# EnsembleEight.net
KiCad netlist of a schematic drawn in EAGLE
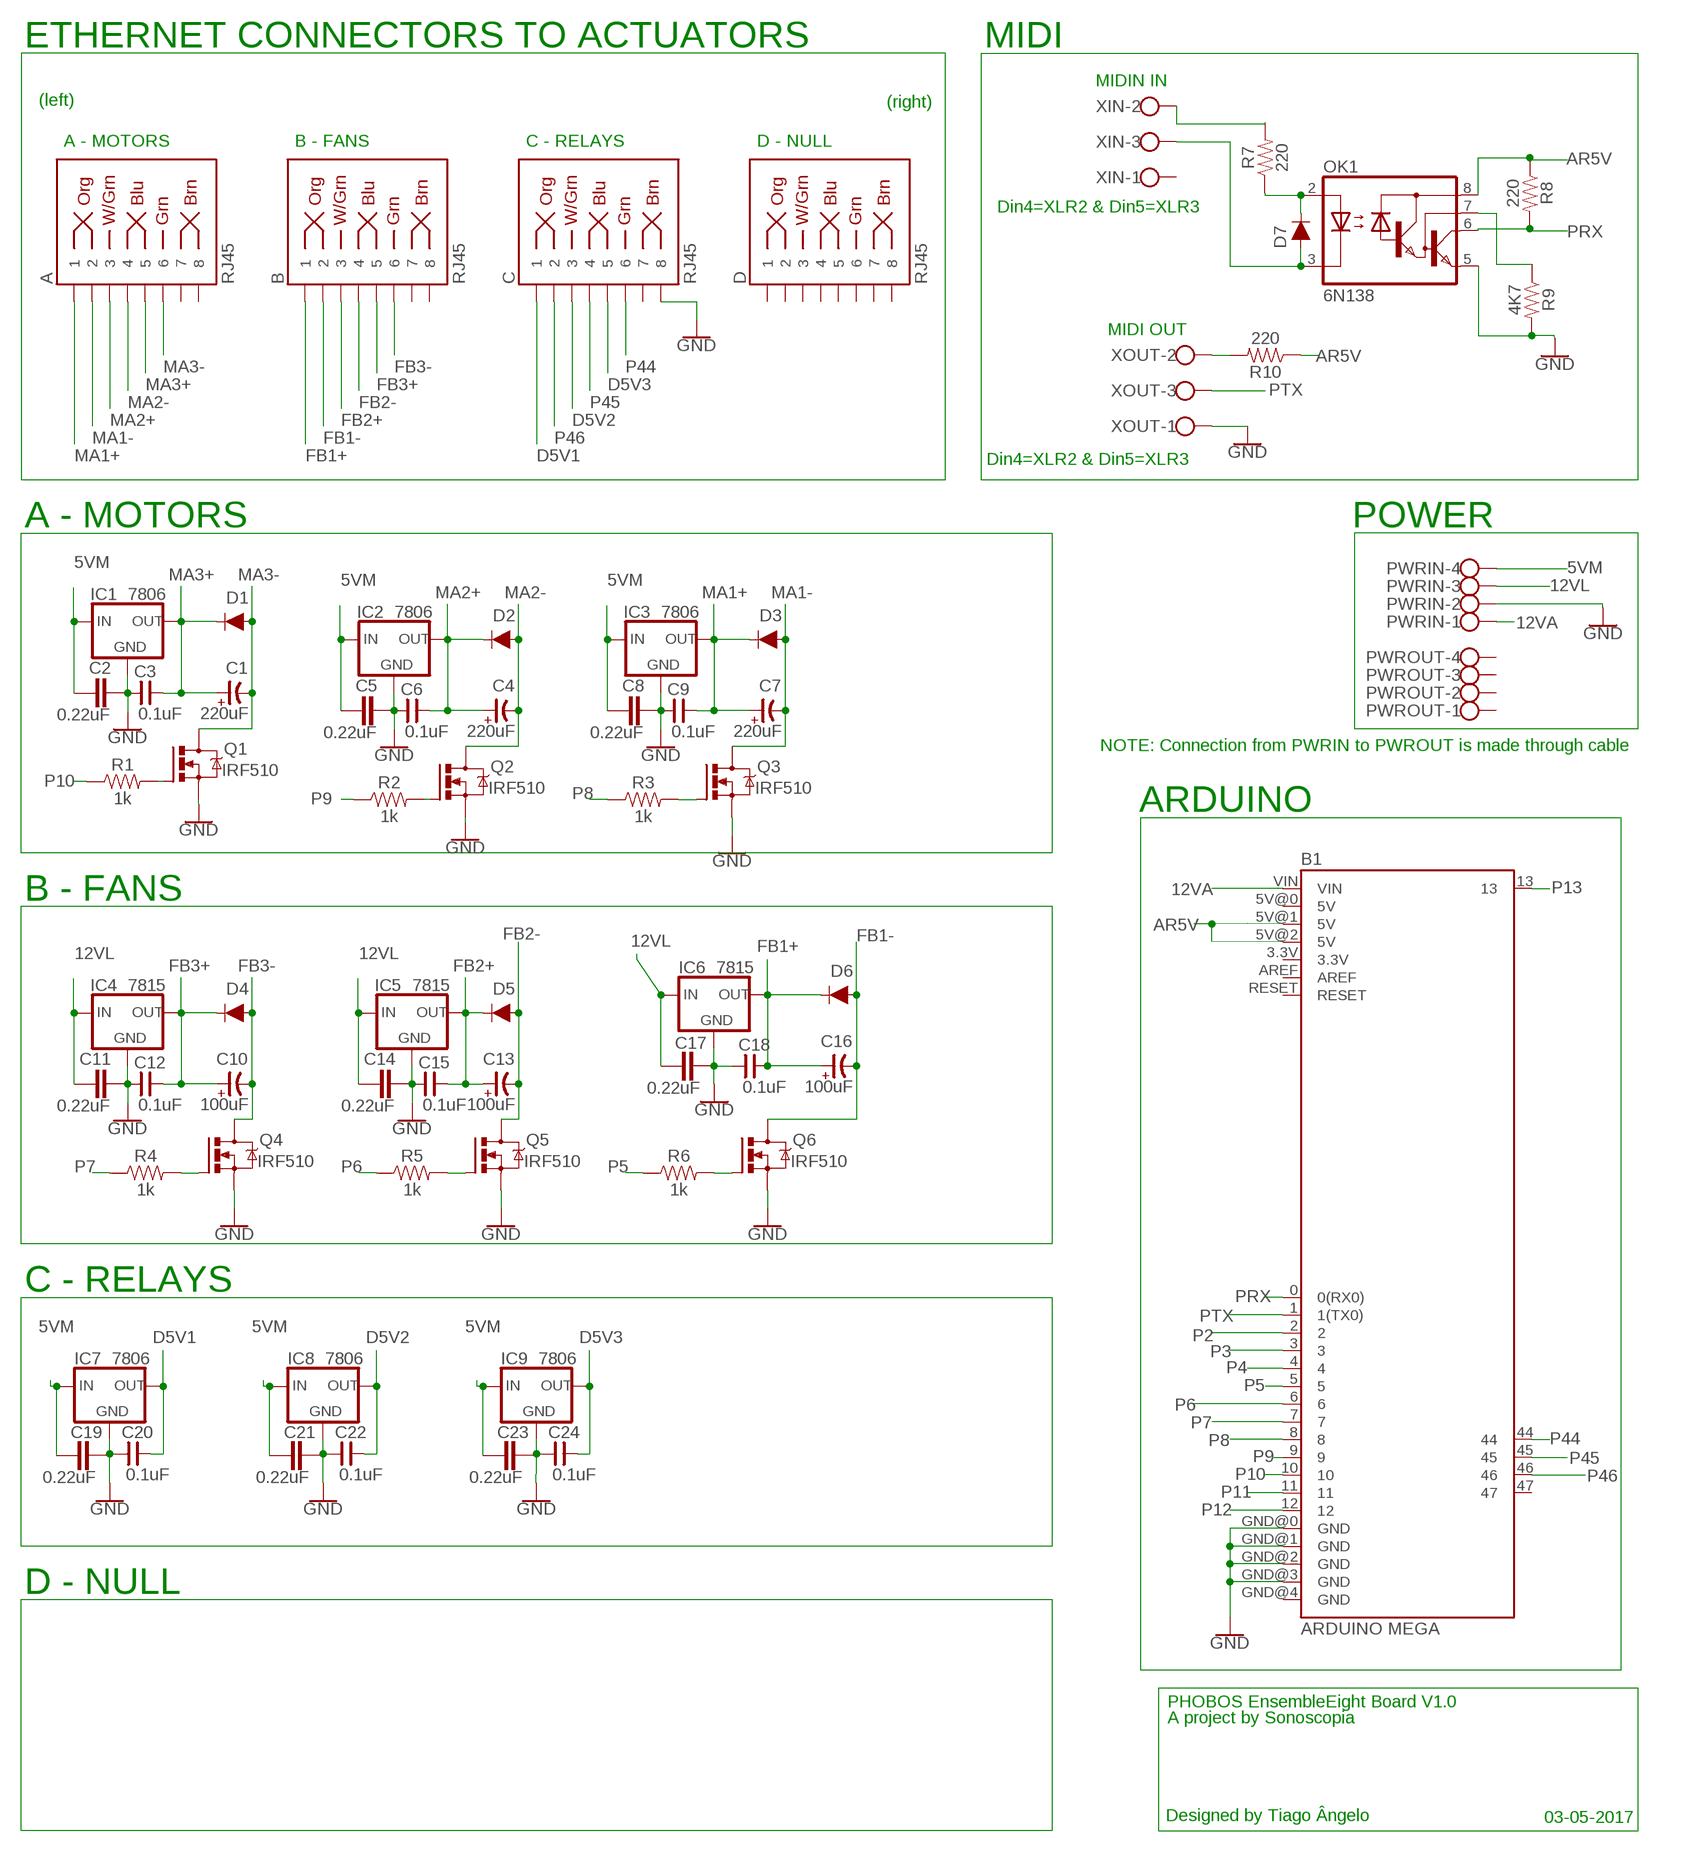
[diagram p0: schematic, sheet 1]

(export (version "E")
  (design (tool "Eeschema 10.0.6"))
  (components
    (comp (ref "A")
      (value "RJ45")
      (footprint "eagle-import:RJ45-8")
      (libsource (lib "eagle-import") (part "RJ45-8"))
    )
    (comp (ref "B")
      (value "RJ45")
      (footprint "eagle-import:RJ45-8")
      (libsource (lib "eagle-import") (part "RJ45-8"))
    )
    (comp (ref "B1")
      (value "ARDUINO MEGA")
      (footprint "eagle-import:ARDUINO_MEGA")
      (libsource (lib "eagle-import") (part "ARDUINO_MEGA_R3FULL"))
    )
    (comp (ref "C")
      (value "RJ45")
      (footprint "eagle-import:RJ45-8")
      (libsource (lib "eagle-import") (part "RJ45-8"))
    )
    (comp (ref "C1")
      (value "220uF")
      (footprint "eagle-import:E-035X080")
      (libsource (lib "eagle-import") (part "CP-E-035X080"))
    )
    (comp (ref "C2")
      (value "0.22uF")
      (footprint "eagle-import:C5B3")
      (libsource (lib "eagle-import") (part "C5/3"))
    )
    (comp (ref "C3")
      (value "0.1uF")
      (footprint "eagle-import:C025-050X025")
      (libsource (lib "eagle-import") (part "CNP-C025-050X025"))
    )
    (comp (ref "C4")
      (value "220uF")
      (footprint "eagle-import:E-035X080")
      (libsource (lib "eagle-import") (part "CP-E-035X080"))
    )
    (comp (ref "C5")
      (value "0.22uF")
      (footprint "eagle-import:C5B3")
      (libsource (lib "eagle-import") (part "C5/3"))
    )
    (comp (ref "C6")
      (value "0.1uF")
      (footprint "eagle-import:C025-050X025")
      (libsource (lib "eagle-import") (part "CNP-C025-050X025"))
    )
    (comp (ref "C7")
      (value "220uF")
      (footprint "eagle-import:E-035X080")
      (libsource (lib "eagle-import") (part "CP-E-035X080"))
    )
    (comp (ref "C8")
      (value "0.22uF")
      (footprint "eagle-import:C5B3")
      (libsource (lib "eagle-import") (part "C5/3"))
    )
    (comp (ref "C9")
      (value "0.1uF")
      (footprint "eagle-import:C025-050X025")
      (libsource (lib "eagle-import") (part "CNP-C025-050X025"))
    )
    (comp (ref "C10")
      (value "100uF")
      (footprint "eagle-import:CAP-MASTER_E-020X050")
      (libsource (lib "eagle-import") (part "CAP-MASTER_CP-E-020X050"))
    )
    (comp (ref "C11")
      (value "0.22uF")
      (footprint "eagle-import:C5B3")
      (libsource (lib "eagle-import") (part "C5/3"))
    )
    (comp (ref "C12")
      (value "0.1uF")
      (footprint "eagle-import:C025-050X025")
      (libsource (lib "eagle-import") (part "CNP-C025-050X025"))
    )
    (comp (ref "C13")
      (value "100uF")
      (footprint "eagle-import:CAP-MASTER_E-020X050")
      (libsource (lib "eagle-import") (part "CAP-MASTER_CP-E-020X050"))
    )
    (comp (ref "C14")
      (value "0.22uF")
      (footprint "eagle-import:C5B3")
      (libsource (lib "eagle-import") (part "C5/3"))
    )
    (comp (ref "C15")
      (value "0.1uF")
      (footprint "eagle-import:C025-050X025")
      (libsource (lib "eagle-import") (part "CNP-C025-050X025"))
    )
    (comp (ref "C16")
      (value "100uF")
      (footprint "eagle-import:CAP-MASTER_E-020X050")
      (libsource (lib "eagle-import") (part "CAP-MASTER_CP-E-020X050"))
    )
    (comp (ref "C17")
      (value "0.22uF")
      (footprint "eagle-import:C5B3")
      (libsource (lib "eagle-import") (part "C5/3"))
    )
    (comp (ref "C18")
      (value "0.1uF")
      (footprint "eagle-import:C025-050X025")
      (libsource (lib "eagle-import") (part "CNP-C025-050X025"))
    )
    (comp (ref "C19")
      (value "0.22uF")
      (footprint "eagle-import:C5B3")
      (libsource (lib "eagle-import") (part "C5/3"))
    )
    (comp (ref "C20")
      (value "0.1uF")
      (footprint "eagle-import:C025-050X025")
      (libsource (lib "eagle-import") (part "CNP-C025-050X025"))
    )
    (comp (ref "C21")
      (value "0.22uF")
      (footprint "eagle-import:C5B3")
      (libsource (lib "eagle-import") (part "C5/3"))
    )
    (comp (ref "C22")
      (value "0.1uF")
      (footprint "eagle-import:C025-050X025")
      (libsource (lib "eagle-import") (part "CNP-C025-050X025"))
    )
    (comp (ref "C23")
      (value "0.22uF")
      (footprint "eagle-import:C5B3")
      (libsource (lib "eagle-import") (part "C5/3"))
    )
    (comp (ref "C24")
      (value "0.1uF")
      (footprint "eagle-import:C025-050X025")
      (libsource (lib "eagle-import") (part "CNP-C025-050X025"))
    )
    (comp (ref "D")
      (value "RJ45")
      (footprint "eagle-import:RJ45-8")
      (libsource (lib "eagle-import") (part "RJ45-8"))
    )
    (comp (ref "D1")
      (value "1A/50V/1.1V")
      (footprint "eagle-import:DIODE-1N4001-KIT")
      (libsource (lib "eagle-import") (part "DIODE-KIT2"))
    )
    (comp (ref "D2")
      (value "1A/50V/1.1V")
      (footprint "eagle-import:DIODE-1N4001-KIT")
      (libsource (lib "eagle-import") (part "DIODE-KIT2"))
    )
    (comp (ref "D3")
      (value "1A/50V/1.1V")
      (footprint "eagle-import:DIODE-1N4001-KIT")
      (libsource (lib "eagle-import") (part "DIODE-KIT2"))
    )
    (comp (ref "D4")
      (value "1A/50V/1.1V")
      (footprint "eagle-import:DIODE-1N4001-KIT")
      (libsource (lib "eagle-import") (part "DIODE-KIT2"))
    )
    (comp (ref "D5")
      (value "1A/50V/1.1V")
      (footprint "eagle-import:DIODE-1N4001-KIT")
      (libsource (lib "eagle-import") (part "DIODE-KIT2"))
    )
    (comp (ref "D6")
      (value "1A/50V/1.1V")
      (footprint "eagle-import:DIODE-1N4001-KIT")
      (libsource (lib "eagle-import") (part "DIODE-KIT2"))
    )
    (comp (ref "D7")
      (value "200mA/100V/1V")
      (footprint "eagle-import:DIODE-1N4148")
      (libsource (lib "eagle-import") (part "DIODE-1N4148"))
    )
    (comp (ref "IC1")
      (value "7806")
      (footprint "eagle-import:78XXS")
      (libsource (lib "eagle-import") (part "78XXS"))
    )
    (comp (ref "IC2")
      (value "7806")
      (footprint "eagle-import:78XXS")
      (libsource (lib "eagle-import") (part "78XXS"))
    )
    (comp (ref "IC3")
      (value "7806")
      (footprint "eagle-import:78XXS")
      (libsource (lib "eagle-import") (part "78XXS"))
    )
    (comp (ref "IC4")
      (value "7815")
      (footprint "eagle-import:78XXS")
      (libsource (lib "eagle-import") (part "78XXS"))
    )
    (comp (ref "IC5")
      (value "7815")
      (footprint "eagle-import:78XXS")
      (libsource (lib "eagle-import") (part "78XXS"))
    )
    (comp (ref "IC6")
      (value "7815")
      (footprint "eagle-import:78XXS")
      (libsource (lib "eagle-import") (part "78XXS"))
    )
    (comp (ref "IC7")
      (value "7806")
      (footprint "eagle-import:78XXS")
      (libsource (lib "eagle-import") (part "78XXS"))
    )
    (comp (ref "IC8")
      (value "7806")
      (footprint "eagle-import:78XXS")
      (libsource (lib "eagle-import") (part "78XXS"))
    )
    (comp (ref "IC9")
      (value "7806")
      (footprint "eagle-import:78XXS")
      (libsource (lib "eagle-import") (part "78XXS"))
    )
    (comp (ref "OK1")
      (value "6N138")
      (footprint "eagle-import:DIL08")
      (fields (field (name "MF") "VISHAY/TELEFUNKEN"))
      (libsource (lib "eagle-import") (part "6N138"))
    )
    (comp (ref "PWRIN")
      (value "W237-4")
      (footprint "eagle-import:W237-4")
      (libsource (lib "eagle-import") (part "W237-4"))
    )
    (comp (ref "PWROUT")
      (value "W237-4")
      (footprint "eagle-import:W237-4")
      (libsource (lib "eagle-import") (part "W237-4"))
    )
    (comp (ref "Q1")
      (value "IRF510")
      (footprint "eagle-import:TO220BV")
      (libsource (lib "eagle-import") (part "IRF520"))
    )
    (comp (ref "Q2")
      (value "IRF510")
      (footprint "eagle-import:TO220BV")
      (libsource (lib "eagle-import") (part "IRF520"))
    )
    (comp (ref "Q3")
      (value "IRF510")
      (footprint "eagle-import:TO220BV")
      (libsource (lib "eagle-import") (part "IRF520"))
    )
    (comp (ref "Q4")
      (value "IRF510")
      (footprint "eagle-import:TO220BV")
      (libsource (lib "eagle-import") (part "IRF520"))
    )
    (comp (ref "Q5")
      (value "IRF510")
      (footprint "eagle-import:TO220BV")
      (libsource (lib "eagle-import") (part "IRF520"))
    )
    (comp (ref "Q6")
      (value "IRF510")
      (footprint "eagle-import:TO220BV")
      (libsource (lib "eagle-import") (part "IRF520"))
    )
    (comp (ref "R1")
      (value "1k")
      (footprint "eagle-import:AXIAL-0.1")
      (libsource (lib "eagle-import") (part "1KOHM-VERT-1/4W-1%"))
    )
    (comp (ref "R2")
      (value "1k")
      (footprint "eagle-import:AXIAL-0.1")
      (libsource (lib "eagle-import") (part "1KOHM-VERT-1/4W-1%"))
    )
    (comp (ref "R3")
      (value "1k")
      (footprint "eagle-import:AXIAL-0.1")
      (libsource (lib "eagle-import") (part "1KOHM-VERT-1/4W-1%"))
    )
    (comp (ref "R4")
      (value "1k")
      (footprint "eagle-import:AXIAL-0.1")
      (libsource (lib "eagle-import") (part "1KOHM-VERT-1/4W-1%"))
    )
    (comp (ref "R5")
      (value "1k")
      (footprint "eagle-import:AXIAL-0.1")
      (libsource (lib "eagle-import") (part "1KOHM-VERT-1/4W-1%"))
    )
    (comp (ref "R6")
      (value "1k")
      (footprint "eagle-import:AXIAL-0.1")
      (libsource (lib "eagle-import") (part "1KOHM-VERT-1/4W-1%"))
    )
    (comp (ref "R7")
      (value "220")
      (footprint "eagle-import:AXIAL-0.3")
      (libsource (lib "eagle-import") (part "1KOHM-HORIZ-1/4W-5%"))
    )
    (comp (ref "R8")
      (value "220")
      (footprint "eagle-import:AXIAL-0.3")
      (libsource (lib "eagle-import") (part "1KOHM-HORIZ-1/4W-5%"))
    )
    (comp (ref "R9")
      (value "4K7")
      (footprint "eagle-import:AXIAL-0.3")
      (libsource (lib "eagle-import") (part "1KOHM-HORIZ-1/4W-5%"))
    )
    (comp (ref "R10")
      (value "220")
      (footprint "eagle-import:AXIAL-0.3")
      (libsource (lib "eagle-import") (part "1KOHM-HORIZ-1/4W-5%"))
    )
    (comp (ref "XIN")
      (value "W237-103")
      (footprint "eagle-import:W237-103")
      (fields (field (name "MPN") "237-103"))
      (libsource (lib "eagle-import") (part "W237-103"))
    )
    (comp (ref "XOUT")
      (value "W237-103")
      (footprint "eagle-import:W237-103")
      (fields (field (name "MPN") "237-103"))
      (libsource (lib "eagle-import") (part "W237-103"))
    )
  )
  (nets
    (net (code "1") (name "/5VM") (class "Default")
      (node (ref "C19") (pin "1") (pinfunction "1_1") (pintype "passive"))
      (node (ref "C2") (pin "1") (pinfunction "1_1") (pintype "passive"))
      (node (ref "C21") (pin "1") (pinfunction "1_1") (pintype "passive"))
      (node (ref "C23") (pin "1") (pinfunction "1_1") (pintype "passive"))
      (node (ref "C5") (pin "1") (pinfunction "1_1") (pintype "passive"))
      (node (ref "C8") (pin "1") (pinfunction "1_1") (pintype "passive"))
      (node (ref "IC1") (pin "IN") (pinfunction "IN_IN") (pintype "input"))
      (node (ref "IC2") (pin "IN") (pinfunction "IN_IN") (pintype "input"))
      (node (ref "IC3") (pin "IN") (pinfunction "IN_IN") (pintype "input"))
      (node (ref "IC7") (pin "IN") (pinfunction "IN_IN") (pintype "input"))
      (node (ref "IC8") (pin "IN") (pinfunction "IN_IN") (pintype "input"))
      (node (ref "IC9") (pin "IN") (pinfunction "IN_IN") (pintype "input"))
      (node (ref "PWRIN") (pin "4") (pinfunction "KL_4") (pintype "passive"))
    )
    (net (code "2") (name "/12VA") (class "Default")
      (node (ref "B1") (pin "VIN") (pinfunction "VIN_VIN") (pintype "bidirectional"))
      (node (ref "PWRIN") (pin "1") (pinfunction "KL_1") (pintype "passive"))
    )
    (net (code "3") (name "/12VL") (class "Default")
      (node (ref "C11") (pin "1") (pinfunction "1_1") (pintype "passive"))
      (node (ref "C14") (pin "1") (pinfunction "1_1") (pintype "passive"))
      (node (ref "C17") (pin "1") (pinfunction "1_1") (pintype "passive"))
      (node (ref "IC4") (pin "IN") (pinfunction "IN_IN") (pintype "input"))
      (node (ref "IC5") (pin "IN") (pinfunction "IN_IN") (pintype "input"))
      (node (ref "IC6") (pin "IN") (pinfunction "IN_IN") (pintype "input"))
      (node (ref "PWRIN") (pin "3") (pinfunction "KL_3") (pintype "passive"))
    )
    (net (code "4") (name "/AR5V") (class "Default")
      (node (ref "B1") (pin "5V@1") (pinfunction "5V_5V@1") (pintype "bidirectional"))
      (node (ref "B1") (pin "5V@2") (pinfunction "5V_5V@2") (pintype "bidirectional"))
      (node (ref "OK1") (pin "8") (pinfunction "VCC_8") (pintype "passive"))
      (node (ref "R10") (pin "P$1") (pinfunction "1_P$1") (pintype "passive"))
      (node (ref "R8") (pin "P$1") (pinfunction "1_P$1") (pintype "passive"))
    )
    (net (code "5") (name "/D5V1") (class "Default")
      (node (ref "C") (pin "1") (pinfunction "1_1") (pintype "bidirectional"))
      (node (ref "C20") (pin "2") (pinfunction "2_2") (pintype "passive"))
      (node (ref "IC7") (pin "OUT") (pinfunction "OUT_OUT") (pintype "passive"))
    )
    (net (code "6") (name "/D5V2") (class "Default")
      (node (ref "C") (pin "3") (pinfunction "3_3") (pintype "bidirectional"))
      (node (ref "C22") (pin "2") (pinfunction "2_2") (pintype "passive"))
      (node (ref "IC8") (pin "OUT") (pinfunction "OUT_OUT") (pintype "passive"))
    )
    (net (code "7") (name "/D5V3") (class "Default")
      (node (ref "C") (pin "5") (pinfunction "5_5") (pintype "bidirectional"))
      (node (ref "C24") (pin "2") (pinfunction "2_2") (pintype "passive"))
      (node (ref "IC9") (pin "OUT") (pinfunction "OUT_OUT") (pintype "passive"))
    )
    (net (code "8") (name "/FB1+") (class "Default")
      (node (ref "B") (pin "1") (pinfunction "1_1") (pintype "bidirectional"))
      (node (ref "C16") (pin "+") (pinfunction "+_+") (pintype "passive"))
      (node (ref "C18") (pin "2") (pinfunction "2_2") (pintype "passive"))
      (node (ref "D6") (pin "C") (pinfunction "C_C") (pintype "passive"))
      (node (ref "IC6") (pin "OUT") (pinfunction "OUT_OUT") (pintype "passive"))
    )
    (net (code "9") (name "/FB1-") (class "Default")
      (node (ref "B") (pin "2") (pinfunction "2_2") (pintype "bidirectional"))
      (node (ref "C16") (pin "-") (pinfunction "-_-") (pintype "passive"))
      (node (ref "D6") (pin "A") (pinfunction "A_A") (pintype "passive"))
      (node (ref "Q6") (pin "D") (pinfunction "D_D") (pintype "passive"))
    )
    (net (code "10") (name "/FB2+") (class "Default")
      (node (ref "B") (pin "3") (pinfunction "3_3") (pintype "bidirectional"))
      (node (ref "C13") (pin "+") (pinfunction "+_+") (pintype "passive"))
      (node (ref "C15") (pin "2") (pinfunction "2_2") (pintype "passive"))
      (node (ref "D5") (pin "C") (pinfunction "C_C") (pintype "passive"))
      (node (ref "IC5") (pin "OUT") (pinfunction "OUT_OUT") (pintype "passive"))
    )
    (net (code "11") (name "/FB2-") (class "Default")
      (node (ref "B") (pin "4") (pinfunction "4_4") (pintype "bidirectional"))
      (node (ref "C13") (pin "-") (pinfunction "-_-") (pintype "passive"))
      (node (ref "D5") (pin "A") (pinfunction "A_A") (pintype "passive"))
      (node (ref "Q5") (pin "D") (pinfunction "D_D") (pintype "passive"))
    )
    (net (code "12") (name "/FB3+") (class "Default")
      (node (ref "B") (pin "5") (pinfunction "5_5") (pintype "bidirectional"))
      (node (ref "C10") (pin "+") (pinfunction "+_+") (pintype "passive"))
      (node (ref "C12") (pin "2") (pinfunction "2_2") (pintype "passive"))
      (node (ref "D4") (pin "C") (pinfunction "C_C") (pintype "passive"))
      (node (ref "IC4") (pin "OUT") (pinfunction "OUT_OUT") (pintype "passive"))
    )
    (net (code "13") (name "/FB3-") (class "Default")
      (node (ref "B") (pin "6") (pinfunction "6_6") (pintype "bidirectional"))
      (node (ref "C10") (pin "-") (pinfunction "-_-") (pintype "passive"))
      (node (ref "D4") (pin "A") (pinfunction "A_A") (pintype "passive"))
      (node (ref "Q4") (pin "D") (pinfunction "D_D") (pintype "passive"))
    )
    (net (code "14") (name "/MA1+") (class "Default")
      (node (ref "A") (pin "1") (pinfunction "1_1") (pintype "bidirectional"))
      (node (ref "C7") (pin "+") (pinfunction "+_+") (pintype "passive"))
      (node (ref "C9") (pin "2") (pinfunction "2_2") (pintype "passive"))
      (node (ref "D3") (pin "C") (pinfunction "C_C") (pintype "passive"))
      (node (ref "IC3") (pin "OUT") (pinfunction "OUT_OUT") (pintype "passive"))
    )
    (net (code "15") (name "/MA1-") (class "Default")
      (node (ref "A") (pin "2") (pinfunction "2_2") (pintype "bidirectional"))
      (node (ref "C7") (pin "-") (pinfunction "-_-") (pintype "passive"))
      (node (ref "D3") (pin "A") (pinfunction "A_A") (pintype "passive"))
      (node (ref "Q3") (pin "D") (pinfunction "D_D") (pintype "passive"))
    )
    (net (code "16") (name "/MA2+") (class "Default")
      (node (ref "A") (pin "3") (pinfunction "3_3") (pintype "bidirectional"))
      (node (ref "C4") (pin "+") (pinfunction "+_+") (pintype "passive"))
      (node (ref "C6") (pin "2") (pinfunction "2_2") (pintype "passive"))
      (node (ref "D2") (pin "C") (pinfunction "C_C") (pintype "passive"))
      (node (ref "IC2") (pin "OUT") (pinfunction "OUT_OUT") (pintype "passive"))
    )
    (net (code "17") (name "/MA2-") (class "Default")
      (node (ref "A") (pin "4") (pinfunction "4_4") (pintype "bidirectional"))
      (node (ref "C4") (pin "-") (pinfunction "-_-") (pintype "passive"))
      (node (ref "D2") (pin "A") (pinfunction "A_A") (pintype "passive"))
      (node (ref "Q2") (pin "D") (pinfunction "D_D") (pintype "passive"))
    )
    (net (code "18") (name "/MA3+") (class "Default")
      (node (ref "A") (pin "5") (pinfunction "5_5") (pintype "bidirectional"))
      (node (ref "C1") (pin "+") (pinfunction "+_+") (pintype "passive"))
      (node (ref "C3") (pin "2") (pinfunction "2_2") (pintype "passive"))
      (node (ref "D1") (pin "C") (pinfunction "C_C") (pintype "passive"))
      (node (ref "IC1") (pin "OUT") (pinfunction "OUT_OUT") (pintype "passive"))
    )
    (net (code "19") (name "/MA3-") (class "Default")
      (node (ref "A") (pin "6") (pinfunction "6_6") (pintype "bidirectional"))
      (node (ref "C1") (pin "-") (pinfunction "-_-") (pintype "passive"))
      (node (ref "D1") (pin "A") (pinfunction "A_A") (pintype "passive"))
      (node (ref "Q1") (pin "D") (pinfunction "D_D") (pintype "passive"))
    )
    (net (code "20") (name "/P2") (class "Default")
      (node (ref "B1") (pin "2") (pinfunction "2_2") (pintype "bidirectional"))
    )
    (net (code "21") (name "/P3") (class "Default")
      (node (ref "B1") (pin "3") (pinfunction "3_3") (pintype "bidirectional"))
    )
    (net (code "22") (name "/P4") (class "Default")
      (node (ref "B1") (pin "4") (pinfunction "4_4") (pintype "bidirectional"))
    )
    (net (code "23") (name "/P5") (class "Default")
      (node (ref "B1") (pin "5") (pinfunction "5_5") (pintype "bidirectional"))
      (node (ref "R6") (pin "P$1") (pinfunction "1_P$1") (pintype "passive"))
    )
    (net (code "24") (name "/P6") (class "Default")
      (node (ref "B1") (pin "6") (pinfunction "6_6") (pintype "bidirectional"))
      (node (ref "R5") (pin "P$1") (pinfunction "1_P$1") (pintype "passive"))
    )
    (net (code "25") (name "/P7") (class "Default")
      (node (ref "B1") (pin "7") (pinfunction "7_7") (pintype "bidirectional"))
      (node (ref "R4") (pin "P$1") (pinfunction "1_P$1") (pintype "passive"))
    )
    (net (code "26") (name "/P8") (class "Default")
      (node (ref "B1") (pin "8") (pinfunction "8_8") (pintype "bidirectional"))
      (node (ref "R3") (pin "P$1") (pinfunction "1_P$1") (pintype "passive"))
    )
    (net (code "27") (name "/P9") (class "Default")
      (node (ref "B1") (pin "9") (pinfunction "9_9") (pintype "bidirectional"))
      (node (ref "R2") (pin "P$1") (pinfunction "1_P$1") (pintype "passive"))
    )
    (net (code "28") (name "/P10") (class "Default")
      (node (ref "B1") (pin "10") (pinfunction "10_10") (pintype "bidirectional"))
      (node (ref "R1") (pin "P$1") (pinfunction "1_P$1") (pintype "passive"))
    )
    (net (code "29") (name "/P11") (class "Default")
      (node (ref "B1") (pin "11") (pinfunction "11_11") (pintype "bidirectional"))
    )
    (net (code "30") (name "/P12") (class "Default")
      (node (ref "B1") (pin "12") (pinfunction "12_12") (pintype "bidirectional"))
    )
    (net (code "31") (name "/P13") (class "Default")
      (node (ref "B1") (pin "13") (pinfunction "13_13") (pintype "bidirectional"))
    )
    (net (code "32") (name "/P44") (class "Default")
      (node (ref "B1") (pin "44") (pinfunction "44_44") (pintype "bidirectional"))
      (node (ref "C") (pin "6") (pinfunction "6_6") (pintype "bidirectional"))
    )
    (net (code "33") (name "/P45") (class "Default")
      (node (ref "B1") (pin "45") (pinfunction "45_45") (pintype "bidirectional"))
      (node (ref "C") (pin "4") (pinfunction "4_4") (pintype "bidirectional"))
    )
    (net (code "34") (name "/P46") (class "Default")
      (node (ref "B1") (pin "46") (pinfunction "46_46") (pintype "bidirectional"))
      (node (ref "C") (pin "2") (pinfunction "2_2") (pintype "bidirectional"))
    )
    (net (code "35") (name "/PRX") (class "Default")
      (node (ref "B1") (pin "0") (pinfunction "0(RX0)_0") (pintype "bidirectional"))
      (node (ref "OK1") (pin "6") (pinfunction "VO_6") (pintype "passive"))
      (node (ref "R8") (pin "P$2") (pinfunction "2_P$2") (pintype "passive"))
    )
    (net (code "36") (name "/PTX") (class "Default")
      (node (ref "B1") (pin "1") (pinfunction "1(TX0)_1") (pintype "bidirectional"))
      (node (ref "XOUT") (pin "3") (pinfunction "KL_3") (pintype "passive"))
    )
    (net (code "37") (name "GND") (class "Default")
      (node (ref "B1") (pin "GND@0") (pinfunction "GND_GND@0") (pintype "bidirectional"))
      (node (ref "B1") (pin "GND@1") (pinfunction "GND_GND@1") (pintype "bidirectional"))
      (node (ref "B1") (pin "GND@2") (pinfunction "GND_GND@2") (pintype "bidirectional"))
      (node (ref "B1") (pin "GND@3") (pinfunction "GND_GND@3") (pintype "bidirectional"))
      (node (ref "C") (pin "8") (pinfunction "8_8") (pintype "bidirectional"))
      (node (ref "C11") (pin "2") (pinfunction "2_2") (pintype "passive"))
      (node (ref "C12") (pin "1") (pinfunction "1_1") (pintype "passive"))
      (node (ref "C14") (pin "2") (pinfunction "2_2") (pintype "passive"))
      (node (ref "C15") (pin "1") (pinfunction "1_1") (pintype "passive"))
      (node (ref "C17") (pin "2") (pinfunction "2_2") (pintype "passive"))
      (node (ref "C18") (pin "1") (pinfunction "1_1") (pintype "passive"))
      (node (ref "C19") (pin "2") (pinfunction "2_2") (pintype "passive"))
      (node (ref "C2") (pin "2") (pinfunction "2_2") (pintype "passive"))
      (node (ref "C20") (pin "1") (pinfunction "1_1") (pintype "passive"))
      (node (ref "C21") (pin "2") (pinfunction "2_2") (pintype "passive"))
      (node (ref "C22") (pin "1") (pinfunction "1_1") (pintype "passive"))
      (node (ref "C23") (pin "2") (pinfunction "2_2") (pintype "passive"))
      (node (ref "C24") (pin "1") (pinfunction "1_1") (pintype "passive"))
      (node (ref "C3") (pin "1") (pinfunction "1_1") (pintype "passive"))
      (node (ref "C5") (pin "2") (pinfunction "2_2") (pintype "passive"))
      (node (ref "C6") (pin "1") (pinfunction "1_1") (pintype "passive"))
      (node (ref "C8") (pin "2") (pinfunction "2_2") (pintype "passive"))
      (node (ref "C9") (pin "1") (pinfunction "1_1") (pintype "passive"))
      (node (ref "IC1") (pin "GND") (pinfunction "GND_GND") (pintype "input"))
      (node (ref "IC2") (pin "GND") (pinfunction "GND_GND") (pintype "input"))
      (node (ref "IC3") (pin "GND") (pinfunction "GND_GND") (pintype "input"))
      (node (ref "IC4") (pin "GND") (pinfunction "GND_GND") (pintype "input"))
      (node (ref "IC5") (pin "GND") (pinfunction "GND_GND") (pintype "input"))
      (node (ref "IC6") (pin "GND") (pinfunction "GND_GND") (pintype "input"))
      (node (ref "IC7") (pin "GND") (pinfunction "GND_GND") (pintype "input"))
      (node (ref "IC8") (pin "GND") (pinfunction "GND_GND") (pintype "input"))
      (node (ref "IC9") (pin "GND") (pinfunction "GND_GND") (pintype "input"))
      (node (ref "OK1") (pin "5") (pinfunction "GND_5") (pintype "passive"))
      (node (ref "PWRIN") (pin "2") (pinfunction "KL_2") (pintype "passive"))
      (node (ref "Q1") (pin "S") (pinfunction "S_S") (pintype "passive"))
      (node (ref "Q2") (pin "S") (pinfunction "S_S") (pintype "passive"))
      (node (ref "Q3") (pin "S") (pinfunction "S_S") (pintype "passive"))
      (node (ref "Q4") (pin "S") (pinfunction "S_S") (pintype "passive"))
      (node (ref "Q5") (pin "S") (pinfunction "S_S") (pintype "passive"))
      (node (ref "Q6") (pin "S") (pinfunction "S_S") (pintype "passive"))
      (node (ref "R9") (pin "P$2") (pinfunction "2_P$2") (pintype "passive"))
      (node (ref "XOUT") (pin "1") (pinfunction "KL_1") (pintype "passive"))
    )
    (net (code "38") (name "Net-(OK1-A)") (class "Default")
      (node (ref "D7") (pin "C") (pinfunction "C_C") (pintype "passive"))
      (node (ref "OK1") (pin "2") (pinfunction "A_2") (pintype "passive"))
      (node (ref "R7") (pin "P$1") (pinfunction "1_P$1") (pintype "passive"))
    )
    (net (code "39") (name "Net-(OK1-C)") (class "Default")
      (node (ref "D7") (pin "A") (pinfunction "A_A") (pintype "passive"))
      (node (ref "OK1") (pin "3") (pinfunction "C_3") (pintype "passive"))
      (node (ref "XIN") (pin "3") (pinfunction "KL_3") (pintype "passive"))
    )
    (net (code "40") (name "Net-(OK1-VB)") (class "Default")
      (node (ref "OK1") (pin "7") (pinfunction "VB_7") (pintype "passive"))
      (node (ref "R9") (pin "P$1") (pinfunction "1_P$1") (pintype "passive"))
    )
    (net (code "41") (name "Net-(R1-2)") (class "Default")
      (node (ref "Q1") (pin "G") (pinfunction "G_G") (pintype "passive"))
      (node (ref "R1") (pin "P$2") (pinfunction "2_P$2") (pintype "passive"))
    )
    (net (code "42") (name "Net-(R2-2)") (class "Default")
      (node (ref "Q2") (pin "G") (pinfunction "G_G") (pintype "passive"))
      (node (ref "R2") (pin "P$2") (pinfunction "2_P$2") (pintype "passive"))
    )
    (net (code "43") (name "Net-(R3-2)") (class "Default")
      (node (ref "Q3") (pin "G") (pinfunction "G_G") (pintype "passive"))
      (node (ref "R3") (pin "P$2") (pinfunction "2_P$2") (pintype "passive"))
    )
    (net (code "44") (name "Net-(R4-2)") (class "Default")
      (node (ref "Q4") (pin "G") (pinfunction "G_G") (pintype "passive"))
      (node (ref "R4") (pin "P$2") (pinfunction "2_P$2") (pintype "passive"))
    )
    (net (code "45") (name "Net-(R5-2)") (class "Default")
      (node (ref "Q5") (pin "G") (pinfunction "G_G") (pintype "passive"))
      (node (ref "R5") (pin "P$2") (pinfunction "2_P$2") (pintype "passive"))
    )
    (net (code "46") (name "Net-(R6-2)") (class "Default")
      (node (ref "Q6") (pin "G") (pinfunction "G_G") (pintype "passive"))
      (node (ref "R6") (pin "P$2") (pinfunction "2_P$2") (pintype "passive"))
    )
    (net (code "47") (name "Net-(R7-2)") (class "Default")
      (node (ref "R7") (pin "P$2") (pinfunction "2_P$2") (pintype "passive"))
      (node (ref "XIN") (pin "2") (pinfunction "KL_2") (pintype "passive"))
    )
    (net (code "48") (name "Net-(R10-2)") (class "Default")
      (node (ref "R10") (pin "P$2") (pinfunction "2_P$2") (pintype "passive"))
      (node (ref "XOUT") (pin "2") (pinfunction "KL_2") (pintype "passive"))
    )
    (net (code "49") (name "unconnected-(A-Pad7)") (class "Default")
      (node (ref "A") (pin "7") (pinfunction "7_7") (pintype "bidirectional"))
    )
    (net (code "50") (name "unconnected-(A-Pad8)") (class "Default")
      (node (ref "A") (pin "8") (pinfunction "8_8") (pintype "bidirectional"))
    )
    (net (code "51") (name "unconnected-(B-Pad7)") (class "Default")
      (node (ref "B") (pin "7") (pinfunction "7_7") (pintype "bidirectional"))
    )
    (net (code "52") (name "unconnected-(B-Pad8)") (class "Default")
      (node (ref "B") (pin "8") (pinfunction "8_8") (pintype "bidirectional"))
    )
    (net (code "53") (name "unconnected-(B1-5V-Pad5V@0)") (class "Default")
      (node (ref "B1") (pin "5V@0") (pinfunction "5V_5V@0") (pintype "bidirectional"))
    )
    (net (code "54") (name "unconnected-(B1-GND-PadGND@4)") (class "Default")
      (node (ref "B1") (pin "GND@4") (pinfunction "GND_GND@4") (pintype "bidirectional"))
    )
    (net (code "55") (name "unconnected-(B1-Pad3.3V)") (class "Default")
      (node (ref "B1") (pin "3.3V") (pinfunction "3.3V_3.3V") (pintype "bidirectional"))
    )
    (net (code "56") (name "unconnected-(B1-Pad47)") (class "Default")
      (node (ref "B1") (pin "47") (pinfunction "47_47") (pintype "bidirectional"))
    )
    (net (code "57") (name "unconnected-(B1-PadAREF)") (class "Default")
      (node (ref "B1") (pin "AREF") (pinfunction "AREF_AREF") (pintype "bidirectional"))
    )
    (net (code "58") (name "unconnected-(B1-PadRESET)") (class "Default")
      (node (ref "B1") (pin "RESET") (pinfunction "RESET_RESET") (pintype "bidirectional"))
    )
    (net (code "59") (name "unconnected-(C-Pad7)") (class "Default")
      (node (ref "C") (pin "7") (pinfunction "7_7") (pintype "bidirectional"))
    )
    (net (code "60") (name "unconnected-(D-Pad1)") (class "Default")
      (node (ref "D") (pin "1") (pinfunction "1_1") (pintype "bidirectional"))
    )
    (net (code "61") (name "unconnected-(D-Pad2)") (class "Default")
      (node (ref "D") (pin "2") (pinfunction "2_2") (pintype "bidirectional"))
    )
    (net (code "62") (name "unconnected-(D-Pad3)") (class "Default")
      (node (ref "D") (pin "3") (pinfunction "3_3") (pintype "bidirectional"))
    )
    (net (code "63") (name "unconnected-(D-Pad4)") (class "Default")
      (node (ref "D") (pin "4") (pinfunction "4_4") (pintype "bidirectional"))
    )
    (net (code "64") (name "unconnected-(D-Pad5)") (class "Default")
      (node (ref "D") (pin "5") (pinfunction "5_5") (pintype "bidirectional"))
    )
    (net (code "65") (name "unconnected-(D-Pad6)") (class "Default")
      (node (ref "D") (pin "6") (pinfunction "6_6") (pintype "bidirectional"))
    )
    (net (code "66") (name "unconnected-(D-Pad7)") (class "Default")
      (node (ref "D") (pin "7") (pinfunction "7_7") (pintype "bidirectional"))
    )
    (net (code "67") (name "unconnected-(D-Pad8)") (class "Default")
      (node (ref "D") (pin "8") (pinfunction "8_8") (pintype "bidirectional"))
    )
    (net (code "68") (name "unconnected-(PWROUTA-KL-Pad1)") (class "Default")
      (node (ref "PWROUT") (pin "1") (pinfunction "KL_1") (pintype "passive"))
    )
    (net (code "69") (name "unconnected-(PWROUTB-KL-Pad2)") (class "Default")
      (node (ref "PWROUT") (pin "2") (pinfunction "KL_2") (pintype "passive"))
    )
    (net (code "70") (name "unconnected-(PWROUTC-KL-Pad3)") (class "Default")
      (node (ref "PWROUT") (pin "3") (pinfunction "KL_3") (pintype "passive"))
    )
    (net (code "71") (name "unconnected-(PWROUTD-KL-Pad4)") (class "Default")
      (node (ref "PWROUT") (pin "4") (pinfunction "KL_4") (pintype "passive"))
    )
    (net (code "72") (name "unconnected-(XINA-KL-Pad1)") (class "Default")
      (node (ref "XIN") (pin "1") (pinfunction "KL_1") (pintype "passive"))
    )
  )
)
